# Motor.net
KiCad netlist of a schematic drawn in EAGLE
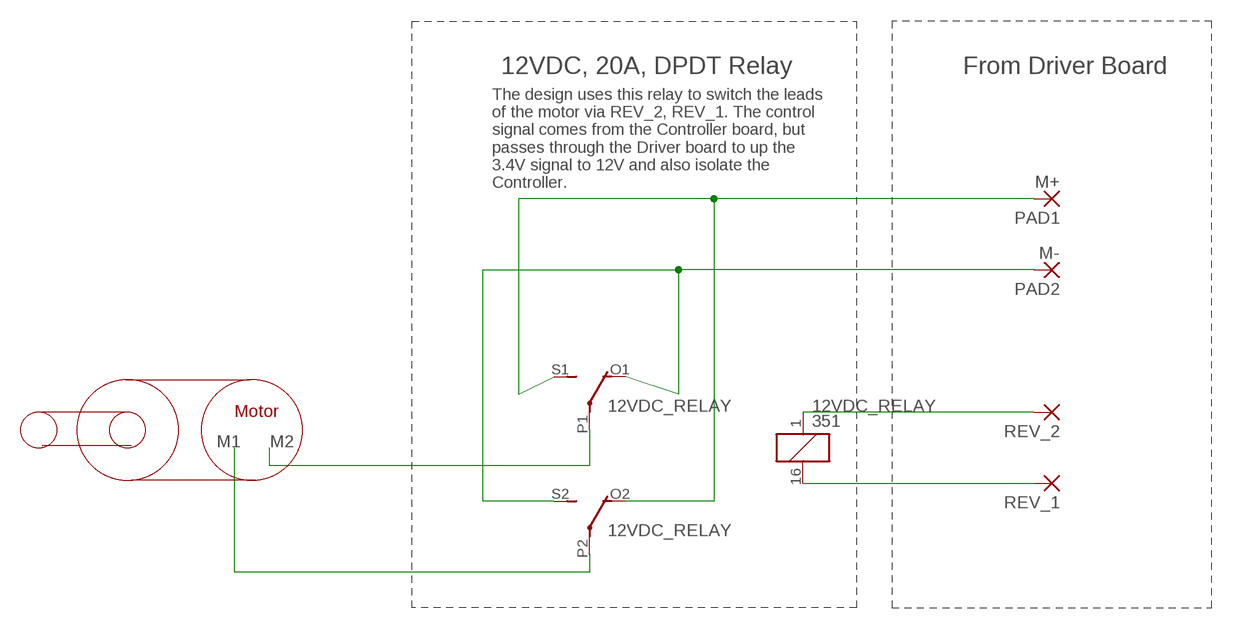
[diagram p0: schematic, sheet 1]

(export (version "E")
  (design (tool "Eeschema 10.0.6"))
  (components
    (comp (ref "12VDC_RELAY")
      (value "351")
      (footprint "eagle-import:351")
      (libsource (lib "eagle-import") (part "351"))
    )
    (comp (ref "PAD1")
      (value "M+")
      (footprint "eagle-import:2,54_0,9")
      (libsource (lib "eagle-import") (part "2,54/0,9"))
    )
    (comp (ref "PAD2")
      (value "M-")
      (footprint "eagle-import:2,54_0,9")
      (libsource (lib "eagle-import") (part "2,54/0,9"))
    )
    (comp (ref "REV_1")
      (value "2,54/0,9")
      (footprint "eagle-import:2,54_0,9")
      (libsource (lib "eagle-import") (part "2,54/0,9"))
    )
    (comp (ref "REV_2")
      (value "2,54/0,9")
      (footprint "eagle-import:2,54_0,9")
      (libsource (lib "eagle-import") (part "2,54/0,9"))
    )
  )
  (nets
    (net (code "1") (name "/M1") (class "Default")
      (node (ref "12VDC_RELAY") (pin "P2") (pinfunction "P_P2") (pintype "passive"))
    )
    (net (code "2") (name "/M2") (class "Default")
      (node (ref "12VDC_RELAY") (pin "P1") (pinfunction "P_P1") (pintype "passive"))
    )
    (net (code "3") (name "Net-(12VDC_RELAYA-2)") (class "Default")
      (node (ref "12VDC_RELAY") (pin "16") (pinfunction "2_16") (pintype "passive"))
      (node (ref "REV_1") (pin "1") (pinfunction "P_1") (pintype "passive"))
    )
    (net (code "4") (name "Net-(12VDC_RELAYB-O)") (class "Default")
      (node (ref "12VDC_RELAY") (pin "O1") (pinfunction "O_O1") (pintype "passive"))
      (node (ref "12VDC_RELAY") (pin "S2") (pinfunction "S_S2") (pintype "passive"))
      (node (ref "PAD2") (pin "1") (pinfunction "P_1") (pintype "passive"))
    )
    (net (code "5") (name "Net-(12VDC_RELAYB-S)") (class "Default")
      (node (ref "12VDC_RELAY") (pin "O2") (pinfunction "O_O2") (pintype "passive"))
      (node (ref "12VDC_RELAY") (pin "S1") (pinfunction "S_S1") (pintype "passive"))
      (node (ref "PAD1") (pin "1") (pinfunction "P_1") (pintype "passive"))
    )
    (net (code "6") (name "Net-(REV_2-P)") (class "Default")
      (node (ref "12VDC_RELAY") (pin "1") (pinfunction "1_1") (pintype "passive"))
      (node (ref "REV_2") (pin "1") (pinfunction "P_1") (pintype "passive"))
    )
  )
)
